# ChipPROHandheld.net
KiCad netlist of a schematic drawn in EAGLE
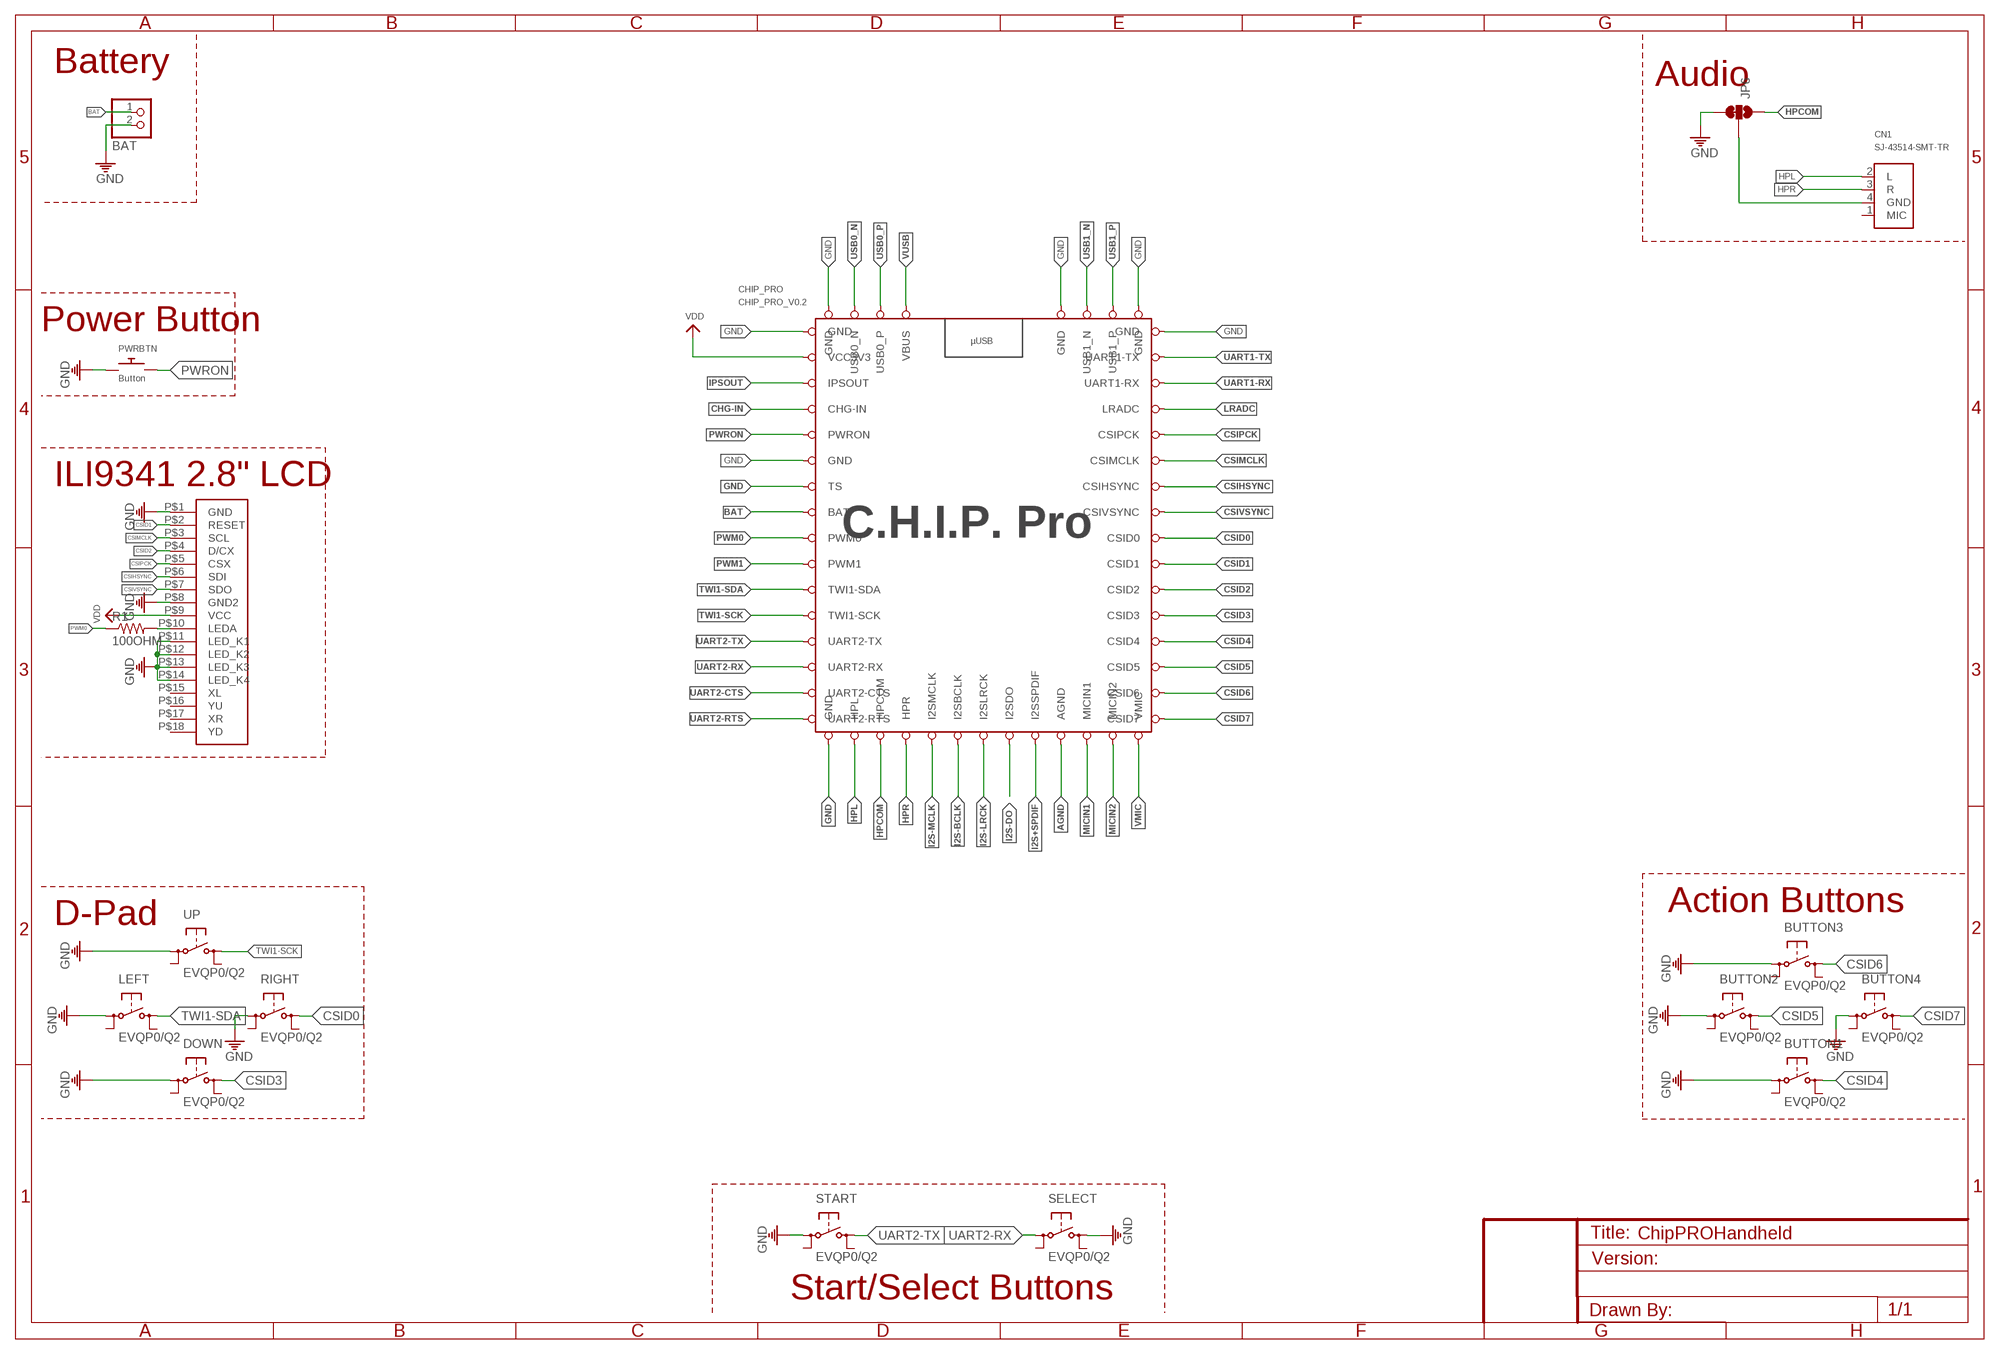
[diagram p0: schematic, sheet 1]

(export (version "E")
  (design (tool "Eeschema 10.0.6"))
  (components
    (comp (ref "BAT")
      (value "JST_2PIN-SMT-RA")
      (footprint "eagle-import:JST-PH-2-SMT-RA")
      (libsource (lib "eagle-import") (part "JST_2PIN-SMT-RA"))
    )
    (comp (ref "BUTTON1")
      (value "EVQP0/Q2")
      (footprint "eagle-import:EVQP0_Q2")
      (libsource (lib "eagle-import") (part "EVQP0/Q2"))
    )
    (comp (ref "BUTTON2")
      (value "EVQP0/Q2")
      (footprint "eagle-import:EVQP0_Q2")
      (libsource (lib "eagle-import") (part "EVQP0/Q2"))
    )
    (comp (ref "BUTTON3")
      (value "EVQP0/Q2")
      (footprint "eagle-import:EVQP0_Q2")
      (libsource (lib "eagle-import") (part "EVQP0/Q2"))
    )
    (comp (ref "BUTTON4")
      (value "EVQP0/Q2")
      (footprint "eagle-import:EVQP0_Q2")
      (libsource (lib "eagle-import") (part "EVQP0/Q2"))
    )
    (comp (ref "CHIP_PRO")
      (value "CHIP_PRO_V0.2")
      (footprint "eagle-import:GR8_MODULE_V0.2")
      (libsource (lib "eagle-import") (part "GR8_MODULE_V0.1"))
    )
    (comp (ref "CN1")
      (value "SJ-43514-SMT-TR")
      (footprint "eagle-import:SJ-43514-SMT-TR")
      (libsource (lib "eagle-import") (part "SJ-43514-SMT-TR"))
    )
    (comp (ref "DOWN")
      (value "EVQP0/Q2")
      (footprint "eagle-import:EVQP0_Q2")
      (libsource (lib "eagle-import") (part "EVQP0/Q2"))
    )
    (comp (ref "JP6")
      (value "JUMPER-PAD-3-2OF3_NC_BY_TRACE_LARGE")
      (footprint "eagle-import:PAD-JUMPER-3-2OF3_NC_BY_TRACE_YES_SILK_LARGE")
      (libsource (lib "eagle-import") (part "JUMPER-PAD-3-2OF3_NC_BY_TRACE_LARGE"))
    )
    (comp (ref "LEFT")
      (value "EVQP0/Q2")
      (footprint "eagle-import:EVQP0_Q2")
      (libsource (lib "eagle-import") (part "EVQP0/Q2"))
    )
    (comp (ref "PWRBTN")
      (value "Button")
      (footprint "eagle-import:BTN_CK_KSS")
      (libsource (lib "eagle-import") (part "SWITCH_PUSHBUTTONC&K_KSS"))
    )
    (comp (ref "R1")
      (value "100OHM")
      (footprint "eagle-import:M0805")
      (libsource (lib "eagle-import") (part "R-US_M0805"))
    )
    (comp (ref "RIGHT")
      (value "EVQP0/Q2")
      (footprint "eagle-import:EVQP0_Q2")
      (libsource (lib "eagle-import") (part "EVQP0/Q2"))
    )
    (comp (ref "SELECT")
      (value "EVQP0/Q2")
      (footprint "eagle-import:EVQP0_Q2")
      (libsource (lib "eagle-import") (part "EVQP0/Q2"))
    )
    (comp (ref "START")
      (value "EVQP0/Q2")
      (footprint "eagle-import:EVQP0_Q2")
      (libsource (lib "eagle-import") (part "EVQP0/Q2"))
    )
    (comp (ref "U$7")
      (value "ILI9341-2.2")
      (footprint "eagle-import:ILI9341")
      (libsource (lib "eagle-import") (part "ILI9341-2.2"))
    )
    (comp (ref "UP")
      (value "EVQP0/Q2")
      (footprint "eagle-import:EVQP0_Q2")
      (libsource (lib "eagle-import") (part "EVQP0/Q2"))
    )
  )
  (nets
    (net (code "1") (name "AGND") (class "Default")
      (node (ref "CHIP_PRO") (pin "AGND") (pinfunction "AGND_AGND") (pintype "power_in"))
    )
    (net (code "2") (name "BAT") (class "Default")
      (node (ref "BAT") (pin "1") (pinfunction "2_1") (pintype "passive"))
      (node (ref "CHIP_PRO") (pin "BAT") (pinfunction "BAT_BAT") (pintype "bidirectional"))
    )
    (net (code "3") (name "CHG-IN") (class "Default")
      (node (ref "CHIP_PRO") (pin "CHG-IN") (pinfunction "CHG-IN_CHG-IN") (pintype "power_in"))
    )
    (net (code "4") (name "CSID0") (class "Default")
      (node (ref "CHIP_PRO") (pin "CSID0") (pinfunction "CSID0_CSID0") (pintype "bidirectional"))
      (node (ref "RIGHT") (pin "3") (pinfunction "S_3") (pintype "passive"))
    )
    (net (code "5") (name "CSID1") (class "Default")
      (node (ref "CHIP_PRO") (pin "CSID1") (pinfunction "CSID1_CSID1") (pintype "bidirectional"))
      (node (ref "U$7") (pin "P$2") (pinfunction "RESET_P$2") (pintype "bidirectional"))
    )
    (net (code "6") (name "CSID2") (class "Default")
      (node (ref "CHIP_PRO") (pin "CSID2") (pinfunction "CSID2_CSID2") (pintype "bidirectional"))
      (node (ref "U$7") (pin "P$4") (pinfunction "D/CX_P$4") (pintype "bidirectional"))
    )
    (net (code "7") (name "CSID3") (class "Default")
      (node (ref "CHIP_PRO") (pin "CSID3") (pinfunction "CSID3_CSID3") (pintype "bidirectional"))
      (node (ref "DOWN") (pin "3") (pinfunction "S_3") (pintype "passive"))
    )
    (net (code "8") (name "CSID4") (class "Default")
      (node (ref "BUTTON1") (pin "3") (pinfunction "S_3") (pintype "passive"))
      (node (ref "CHIP_PRO") (pin "CSID4") (pinfunction "CSID4_CSID4") (pintype "bidirectional"))
    )
    (net (code "9") (name "CSID5") (class "Default")
      (node (ref "BUTTON2") (pin "3") (pinfunction "S_3") (pintype "passive"))
      (node (ref "CHIP_PRO") (pin "CSID5") (pinfunction "CSID5_CSID5") (pintype "bidirectional"))
    )
    (net (code "10") (name "CSID6") (class "Default")
      (node (ref "BUTTON3") (pin "3") (pinfunction "S_3") (pintype "passive"))
      (node (ref "CHIP_PRO") (pin "CSID6") (pinfunction "CSID6_CSID6") (pintype "bidirectional"))
    )
    (net (code "11") (name "CSID7") (class "Default")
      (node (ref "BUTTON4") (pin "3") (pinfunction "S_3") (pintype "passive"))
      (node (ref "CHIP_PRO") (pin "CSID7") (pinfunction "CSID7_CSID7") (pintype "bidirectional"))
    )
    (net (code "12") (name "CSIHSYNC") (class "Default")
      (node (ref "CHIP_PRO") (pin "CSIHSYNC") (pinfunction "CSIHSYNC_CSIHSYNC") (pintype "bidirectional"))
      (node (ref "U$7") (pin "P$6") (pinfunction "SDI_P$6") (pintype "bidirectional"))
    )
    (net (code "13") (name "CSIMCLK") (class "Default")
      (node (ref "CHIP_PRO") (pin "CSIMCLK") (pinfunction "CSIMCLK_CSIMCLK") (pintype "bidirectional"))
      (node (ref "U$7") (pin "P$3") (pinfunction "SCL_P$3") (pintype "bidirectional"))
    )
    (net (code "14") (name "CSIPCK") (class "Default")
      (node (ref "CHIP_PRO") (pin "CSIPCK") (pinfunction "CSIPCK_CSIPCK") (pintype "bidirectional"))
      (node (ref "U$7") (pin "P$5") (pinfunction "CSX_P$5") (pintype "bidirectional"))
    )
    (net (code "15") (name "CSIVSYNC") (class "Default")
      (node (ref "CHIP_PRO") (pin "CSIVSYNC") (pinfunction "CSIVSYNC_CSIVSYNC") (pintype "bidirectional"))
      (node (ref "U$7") (pin "P$7") (pinfunction "SDO_P$7") (pintype "bidirectional"))
    )
    (net (code "16") (name "GND") (class "Default")
      (node (ref "BAT") (pin "2") (pinfunction "1_2") (pintype "passive"))
      (node (ref "BUTTON1") (pin "1") (pinfunction "P_1") (pintype "passive"))
      (node (ref "BUTTON2") (pin "1") (pinfunction "P_1") (pintype "passive"))
      (node (ref "BUTTON3") (pin "1") (pinfunction "P_1") (pintype "passive"))
      (node (ref "BUTTON4") (pin "1") (pinfunction "P_1") (pintype "passive"))
      (node (ref "CHIP_PRO") (pin "GND@0") (pinfunction "GND_GND@0") (pintype "power_in"))
      (node (ref "CHIP_PRO") (pin "GND@1") (pinfunction "GND_GND@1") (pintype "power_in"))
      (node (ref "CHIP_PRO") (pin "GND@2") (pinfunction "GND_GND@2") (pintype "power_in"))
      (node (ref "CHIP_PRO") (pin "GND@3") (pinfunction "GND_GND@3") (pintype "power_in"))
      (node (ref "CHIP_PRO") (pin "GND@4") (pinfunction "GND_GND@4") (pintype "power_in"))
      (node (ref "CHIP_PRO") (pin "GND@6") (pinfunction "GND_GND@6") (pintype "power_in"))
      (node (ref "CHIP_PRO") (pin "GND@7") (pinfunction "GND_GND@7") (pintype "power_in"))
      (node (ref "CHIP_PRO") (pin "TS") (pinfunction "TS_TS") (pintype "bidirectional"))
      (node (ref "DOWN") (pin "1") (pinfunction "P_1") (pintype "passive"))
      (node (ref "JP6") (pin "3") (pinfunction "3_3") (pintype "passive"))
      (node (ref "LEFT") (pin "1") (pinfunction "P_1") (pintype "passive"))
      (node (ref "PWRBTN") (pin "P$1") (pinfunction "P$1_P$1") (pintype "passive"))
      (node (ref "RIGHT") (pin "1") (pinfunction "P_1") (pintype "passive"))
      (node (ref "SELECT") (pin "3") (pinfunction "S_3") (pintype "passive"))
      (node (ref "START") (pin "1") (pinfunction "P_1") (pintype "passive"))
      (node (ref "U$7") (pin "P$1") (pinfunction "GND_P$1") (pintype "bidirectional"))
      (node (ref "U$7") (pin "P$11") (pinfunction "LED_K1_P$11") (pintype "bidirectional"))
      (node (ref "U$7") (pin "P$12") (pinfunction "LED_K2_P$12") (pintype "bidirectional"))
      (node (ref "U$7") (pin "P$13") (pinfunction "LED_K3_P$13") (pintype "bidirectional"))
      (node (ref "U$7") (pin "P$14") (pinfunction "LED_K4_P$14") (pintype "bidirectional"))
      (node (ref "U$7") (pin "P$8") (pinfunction "GND2_P$8") (pintype "bidirectional"))
      (node (ref "UP") (pin "1") (pinfunction "P_1") (pintype "passive"))
    )
    (net (code "17") (name "HPCOM") (class "Default")
      (node (ref "CHIP_PRO") (pin "HPCOM") (pinfunction "HPCOM_HPCOM") (pintype "bidirectional"))
      (node (ref "JP6") (pin "1") (pinfunction "1_1") (pintype "passive"))
    )
    (net (code "18") (name "HPL") (class "Default")
      (node (ref "CHIP_PRO") (pin "HPL") (pinfunction "HPL_HPL") (pintype "bidirectional"))
      (node (ref "CN1") (pin "2") (pinfunction "L_2") (pintype "bidirectional"))
    )
    (net (code "19") (name "HPR") (class "Default")
      (node (ref "CHIP_PRO") (pin "HPR") (pinfunction "HPR_HPR") (pintype "bidirectional"))
      (node (ref "CN1") (pin "3") (pinfunction "R_3") (pintype "bidirectional"))
    )
    (net (code "20") (name "I2S+SPDIF") (class "Default")
      (node (ref "CHIP_PRO") (pin "I2S+SPDIF") (pinfunction "I2SSPDIF_I2S+SPDIF") (pintype "bidirectional"))
    )
    (net (code "21") (name "I2S-BCLK") (class "Default")
      (node (ref "CHIP_PRO") (pin "I2S-BCLK") (pinfunction "I2SBCLK_I2S-BCLK") (pintype "bidirectional"))
    )
    (net (code "22") (name "I2S-DO") (class "Default")
      (node (ref "CHIP_PRO") (pin "I2S-DO") (pinfunction "I2SDO_I2S-DO") (pintype "bidirectional"))
    )
    (net (code "23") (name "I2S-LRCK") (class "Default")
      (node (ref "CHIP_PRO") (pin "I2S-LRCK") (pinfunction "I2SLRCK_I2S-LRCK") (pintype "bidirectional"))
    )
    (net (code "24") (name "I2S-MCLK") (class "Default")
      (node (ref "CHIP_PRO") (pin "I2S-MCLK") (pinfunction "I2SMCLK_I2S-MCLK") (pintype "bidirectional"))
    )
    (net (code "25") (name "IPSOUT") (class "Default")
      (node (ref "CHIP_PRO") (pin "IPSOUT") (pinfunction "IPSOUT_IPSOUT") (pintype "power_in"))
    )
    (net (code "26") (name "LRADC") (class "Default")
      (node (ref "CHIP_PRO") (pin "LRADC") (pinfunction "LRADC_LRADC") (pintype "bidirectional"))
    )
    (net (code "27") (name "MICIN1") (class "Default")
      (node (ref "CHIP_PRO") (pin "MICIN1") (pinfunction "MICIN1_MICIN1") (pintype "bidirectional"))
    )
    (net (code "28") (name "MICIN2") (class "Default")
      (node (ref "CHIP_PRO") (pin "MICIN2") (pinfunction "MICIN2_MICIN2") (pintype "bidirectional"))
    )
    (net (code "29") (name "Net-(CN1-GND)") (class "Default")
      (node (ref "CN1") (pin "4") (pinfunction "GND_4") (pintype "bidirectional"))
      (node (ref "JP6") (pin "2") (pinfunction "2_2") (pintype "passive"))
    )
    (net (code "30") (name "Net-(U$7-LEDA)") (class "Default")
      (node (ref "R1") (pin "2") (pinfunction "2_2") (pintype "passive"))
      (node (ref "U$7") (pin "P$10") (pinfunction "LEDA_P$10") (pintype "bidirectional"))
    )
    (net (code "31") (name "PWM0") (class "Default")
      (node (ref "CHIP_PRO") (pin "PWM0") (pinfunction "PWM0_PWM0") (pintype "bidirectional"))
      (node (ref "R1") (pin "1") (pinfunction "1_1") (pintype "passive"))
    )
    (net (code "32") (name "PWM1") (class "Default")
      (node (ref "CHIP_PRO") (pin "PWM1") (pinfunction "PWM1_PWM1") (pintype "bidirectional"))
    )
    (net (code "33") (name "PWRON") (class "Default")
      (node (ref "CHIP_PRO") (pin "PWRON") (pinfunction "PWRON_PWRON") (pintype "bidirectional"))
      (node (ref "PWRBTN") (pin "P$2") (pinfunction "P$2_P$2") (pintype "passive"))
    )
    (net (code "34") (name "TWI1-SCK") (class "Default")
      (node (ref "CHIP_PRO") (pin "TWI1-SCK") (pinfunction "TWI1-SCK_TWI1-SCK") (pintype "bidirectional"))
      (node (ref "UP") (pin "3") (pinfunction "S_3") (pintype "passive"))
    )
    (net (code "35") (name "TWI1-SDA") (class "Default")
      (node (ref "CHIP_PRO") (pin "TWI1-SDA") (pinfunction "TWI1-SDA_TWI1-SDA") (pintype "bidirectional"))
      (node (ref "LEFT") (pin "3") (pinfunction "S_3") (pintype "passive"))
    )
    (net (code "36") (name "UART1-RX") (class "Default")
      (node (ref "CHIP_PRO") (pin "UART1-RX") (pinfunction "UART1-RX_UART1-RX") (pintype "bidirectional"))
    )
    (net (code "37") (name "UART1-TX") (class "Default")
      (node (ref "CHIP_PRO") (pin "UART1-TX") (pinfunction "UART1-TX_UART1-TX") (pintype "bidirectional"))
    )
    (net (code "38") (name "UART2-CTS") (class "Default")
      (node (ref "CHIP_PRO") (pin "UART2-CTS") (pinfunction "UART2-CTS_UART2-CTS") (pintype "bidirectional"))
    )
    (net (code "39") (name "UART2-RTS") (class "Default")
      (node (ref "CHIP_PRO") (pin "UART2-RTS") (pinfunction "UART2-RTS_UART2-RTS") (pintype "bidirectional"))
    )
    (net (code "40") (name "UART2-RX") (class "Default")
      (node (ref "CHIP_PRO") (pin "UART2-RX") (pinfunction "UART2-RX_UART2-RX") (pintype "bidirectional"))
      (node (ref "SELECT") (pin "1") (pinfunction "P_1") (pintype "passive"))
    )
    (net (code "41") (name "UART2-TX") (class "Default")
      (node (ref "CHIP_PRO") (pin "UART2-TX") (pinfunction "UART2-TX_UART2-TX") (pintype "bidirectional"))
      (node (ref "START") (pin "3") (pinfunction "S_3") (pintype "passive"))
    )
    (net (code "42") (name "USB0_N") (class "Default")
      (node (ref "CHIP_PRO") (pin "USB0_N") (pinfunction "USB0_N_USB0_N") (pintype "bidirectional"))
    )
    (net (code "43") (name "USB0_P") (class "Default")
      (node (ref "CHIP_PRO") (pin "USB0_P") (pinfunction "USB0_P_USB0_P") (pintype "bidirectional"))
    )
    (net (code "44") (name "USB1_N") (class "Default")
      (node (ref "CHIP_PRO") (pin "USB1_N") (pinfunction "USB1_N_USB1_N") (pintype "bidirectional"))
    )
    (net (code "45") (name "USB1_P") (class "Default")
      (node (ref "CHIP_PRO") (pin "USB1_P") (pinfunction "USB1_P_USB1_P") (pintype "bidirectional"))
    )
    (net (code "46") (name "VDD") (class "Default")
      (node (ref "CHIP_PRO") (pin "VCC3V3") (pinfunction "VCC3V3_VCC3V3") (pintype "power_in"))
      (node (ref "U$7") (pin "P$9") (pinfunction "VCC_P$9") (pintype "bidirectional"))
    )
    (net (code "47") (name "VMIC") (class "Default")
      (node (ref "CHIP_PRO") (pin "VMIC") (pinfunction "VMIC_VMIC") (pintype "bidirectional"))
    )
    (net (code "48") (name "VUSB") (class "Default")
      (node (ref "CHIP_PRO") (pin "VBUS") (pinfunction "VBUS_VBUS") (pintype "power_in"))
    )
    (net (code "49") (name "unconnected-(BUTTON1-P1-Pad2)") (class "Default")
      (node (ref "BUTTON1") (pin "2") (pinfunction "P1_2") (pintype "passive"))
    )
    (net (code "50") (name "unconnected-(BUTTON1-S1-Pad4)") (class "Default")
      (node (ref "BUTTON1") (pin "4") (pinfunction "S1_4") (pintype "passive"))
    )
    (net (code "51") (name "unconnected-(BUTTON2-P1-Pad2)") (class "Default")
      (node (ref "BUTTON2") (pin "2") (pinfunction "P1_2") (pintype "passive"))
    )
    (net (code "52") (name "unconnected-(BUTTON2-S1-Pad4)") (class "Default")
      (node (ref "BUTTON2") (pin "4") (pinfunction "S1_4") (pintype "passive"))
    )
    (net (code "53") (name "unconnected-(BUTTON3-P1-Pad2)") (class "Default")
      (node (ref "BUTTON3") (pin "2") (pinfunction "P1_2") (pintype "passive"))
    )
    (net (code "54") (name "unconnected-(BUTTON3-S1-Pad4)") (class "Default")
      (node (ref "BUTTON3") (pin "4") (pinfunction "S1_4") (pintype "passive"))
    )
    (net (code "55") (name "unconnected-(BUTTON4-P1-Pad2)") (class "Default")
      (node (ref "BUTTON4") (pin "2") (pinfunction "P1_2") (pintype "passive"))
    )
    (net (code "56") (name "unconnected-(BUTTON4-S1-Pad4)") (class "Default")
      (node (ref "BUTTON4") (pin "4") (pinfunction "S1_4") (pintype "passive"))
    )
    (net (code "57") (name "unconnected-(CN1-MIC-Pad1)") (class "Default")
      (node (ref "CN1") (pin "1") (pinfunction "MIC_1") (pintype "bidirectional"))
    )
    (net (code "58") (name "unconnected-(DOWN-P1-Pad2)") (class "Default")
      (node (ref "DOWN") (pin "2") (pinfunction "P1_2") (pintype "passive"))
    )
    (net (code "59") (name "unconnected-(DOWN-S1-Pad4)") (class "Default")
      (node (ref "DOWN") (pin "4") (pinfunction "S1_4") (pintype "passive"))
    )
    (net (code "60") (name "unconnected-(LEFT-P1-Pad2)") (class "Default")
      (node (ref "LEFT") (pin "2") (pinfunction "P1_2") (pintype "passive"))
    )
    (net (code "61") (name "unconnected-(LEFT-S1-Pad4)") (class "Default")
      (node (ref "LEFT") (pin "4") (pinfunction "S1_4") (pintype "passive"))
    )
    (net (code "62") (name "unconnected-(RIGHT-P1-Pad2)") (class "Default")
      (node (ref "RIGHT") (pin "2") (pinfunction "P1_2") (pintype "passive"))
    )
    (net (code "63") (name "unconnected-(RIGHT-S1-Pad4)") (class "Default")
      (node (ref "RIGHT") (pin "4") (pinfunction "S1_4") (pintype "passive"))
    )
    (net (code "64") (name "unconnected-(SELECT-P1-Pad2)") (class "Default")
      (node (ref "SELECT") (pin "2") (pinfunction "P1_2") (pintype "passive"))
    )
    (net (code "65") (name "unconnected-(SELECT-S1-Pad4)") (class "Default")
      (node (ref "SELECT") (pin "4") (pinfunction "S1_4") (pintype "passive"))
    )
    (net (code "66") (name "unconnected-(START-P1-Pad2)") (class "Default")
      (node (ref "START") (pin "2") (pinfunction "P1_2") (pintype "passive"))
    )
    (net (code "67") (name "unconnected-(START-S1-Pad4)") (class "Default")
      (node (ref "START") (pin "4") (pinfunction "S1_4") (pintype "passive"))
    )
    (net (code "68") (name "unconnected-(U$7-XL-PadP$15)") (class "Default")
      (node (ref "U$7") (pin "P$15") (pinfunction "XL_P$15") (pintype "bidirectional"))
    )
    (net (code "69") (name "unconnected-(U$7-XR-PadP$17)") (class "Default")
      (node (ref "U$7") (pin "P$17") (pinfunction "XR_P$17") (pintype "bidirectional"))
    )
    (net (code "70") (name "unconnected-(U$7-YD-PadP$18)") (class "Default")
      (node (ref "U$7") (pin "P$18") (pinfunction "YD_P$18") (pintype "bidirectional"))
    )
    (net (code "71") (name "unconnected-(U$7-YU-PadP$16)") (class "Default")
      (node (ref "U$7") (pin "P$16") (pinfunction "YU_P$16") (pintype "bidirectional"))
    )
    (net (code "72") (name "unconnected-(UP-P1-Pad2)") (class "Default")
      (node (ref "UP") (pin "2") (pinfunction "P1_2") (pintype "passive"))
    )
    (net (code "73") (name "unconnected-(UP-S1-Pad4)") (class "Default")
      (node (ref "UP") (pin "4") (pinfunction "S1_4") (pintype "passive"))
    )
  )
)
